# SSRs.net
KiCad netlist of a schematic drawn in Altium Designer
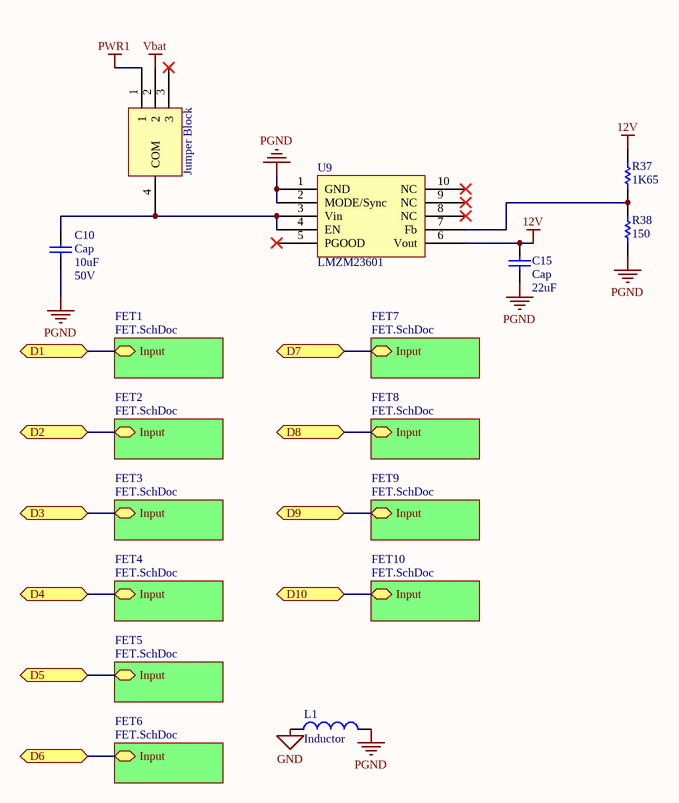
[diagram p0: SSRs.SchDoc]

(export (version "E")
  (design (tool "Eeschema 10.0.6"))
  (components
    (comp (ref "C10")
      (value "Cap")
      (footprint "CAPC3216X180N")
      (description "Capacitor")
      (fields
        (field (name "ALTIUM_VALUE") "10uF")
        (field (name "MANUFACTURER PART NUMBER") "CL31A106MBHNNNE")
        (field (name "VENDOR PART NUMBER") "1276-6736-1-ND")
        (field (name "VOLTAGE RATING") "50V")
      )
      (libsource (lib "Miscellaneous Devices") (part "Cap"))
    )
    (comp (ref "C15")
      (value "Cap")
      (footprint "CAPC3216X180N")
      (description "Capacitor")
      (fields
        (field (name "ALTIUM_VALUE") "22uF")
        (field (name "MANUFACTURER PART NUMBER") "CL31A226KAHNNNE")
        (field (name "VENDOR PART NUMBER") "1276-3047-1-ND")
      )
      (libsource (lib "Miscellaneous Devices") (part "Cap"))
    )
    (comp (ref "J6")
      (value "Jumper Block")
      (footprint "Jumper Block")
      (libsource (lib "BeagleCape") (part "Jumper Block"))
    )
    (comp (ref "L1")
      (value "Inductor")
      (footprint "0402-A")
      (fields
        (field (name "MANUFACTURER PART NUMBER") "MPZ1005S300CT000")
        (field (name "VENDOR PART NUMBER") "445-2979-1-ND")
      )
      (libsource (lib "Miscellaneous Devices") (part "Inductor"))
    )
    (comp (ref "R37")
      (value "1K65")
      (footprint "0402")
      (description "Resistor")
      (fields
        (field (name "MANUFACTURER PART NUMBER") "YAG3043CT-ND")
        (field (name "VENDOR PART NUMBER") "RC0402FR-071K65L")
      )
      (libsource (lib "Miscellaneous Devices") (part "Res1"))
    )
    (comp (ref "R38")
      (value "150")
      (footprint "0402")
      (description "Resistor")
      (fields
        (field (name "MANUFACTURER PART NUMBER") "RC0402FR-07150RL")
        (field (name "VENDOR PART NUMBER") "311-150LRCT-ND")
      )
      (libsource (lib "Miscellaneous Devices") (part "Res1"))
    )
    (comp (ref "U9")
      (value "LMZM23601")
      (footprint "MODULE_LMZM23600V3SILT")
      (fields
        (field (name "MANUFACTURER PART NUMBER") "LMZM23601SILT")
        (field (name "VENDOR PART NUMBER") "296-49460-1-ND")
      )
      (libsource (lib "BeagleCape") (part "LMZM23601"))
    )
  )
  (nets
    (net (code "11") (name "12V") (class "Default")
      (node (ref "C15") (pin "2") (pinfunction "2_2") (pintype "passive"))
      (node (ref "R37") (pin "2") (pinfunction "2_2") (pintype "passive"))
      (node (ref "U9") (pin "6") (pinfunction "Vout_6") (pintype "passive"))
    )
    (net (code "12") (name "GND") (class "Default")
      (node (ref "L1") (pin "1") (pinfunction "1_1") (pintype "passive"))
    )
    (net (code "13") (name "Net-(J6-COM)") (class "Default")
      (node (ref "C10") (pin "2") (pinfunction "2_2") (pintype "passive"))
      (node (ref "J6") (pin "4") (pinfunction "COM_4") (pintype "passive"))
      (node (ref "U9") (pin "3") (pinfunction "Vin_3") (pintype "passive"))
      (node (ref "U9") (pin "4") (pinfunction "EN_4") (pintype "passive"))
    )
    (net (code "14") (name "Net-(U9-Fb)") (class "Default")
      (node (ref "R37") (pin "1") (pinfunction "1_1") (pintype "passive"))
      (node (ref "R38") (pin "2") (pinfunction "2_2") (pintype "passive"))
      (node (ref "U9") (pin "7") (pinfunction "Fb_7") (pintype "passive"))
    )
    (net (code "15") (name "PGND") (class "Default")
      (node (ref "C10") (pin "1") (pinfunction "1_1") (pintype "passive"))
      (node (ref "C15") (pin "1") (pinfunction "1_1") (pintype "passive"))
      (node (ref "L1") (pin "2") (pinfunction "2_2") (pintype "passive"))
      (node (ref "R38") (pin "1") (pinfunction "1_1") (pintype "passive"))
      (node (ref "U9") (pin "1") (pinfunction "GND_1") (pintype "passive"))
      (node (ref "U9") (pin "2") (pinfunction "MODE/Sync_2") (pintype "passive"))
    )
    (net (code "16") (name "PWR1") (class "Default")
      (node (ref "J6") (pin "1") (pinfunction "1_1") (pintype "passive"))
    )
    (net (code "17") (name "Vbat") (class "Default")
      (node (ref "J6") (pin "2") (pinfunction "2_2") (pintype "passive"))
    )
    (net (code "18") (name "unconnected-(J6-Pad3)") (class "Default")
      (node (ref "J6") (pin "3") (pinfunction "3_3") (pintype "passive+no_connect"))
    )
    (net (code "19") (name "unconnected-(U9-NC-Pad8)") (class "Default")
      (node (ref "U9") (pin "8") (pinfunction "NC_8") (pintype "passive+no_connect"))
    )
    (net (code "20") (name "unconnected-(U9-NC-Pad9)") (class "Default")
      (node (ref "U9") (pin "9") (pinfunction "NC_9") (pintype "passive+no_connect"))
    )
    (net (code "21") (name "unconnected-(U9-NC-Pad10)") (class "Default")
      (node (ref "U9") (pin "10") (pinfunction "NC_10") (pintype "passive+no_connect"))
    )
    (net (code "22") (name "unconnected-(U9-PGOOD-Pad5)") (class "Default")
      (node (ref "U9") (pin "5") (pinfunction "PGOOD_5") (pintype "passive+no_connect"))
    )
  )
)
